# 3_IMU_ETH.net
KiCad netlist of a schematic drawn in Altium Designer
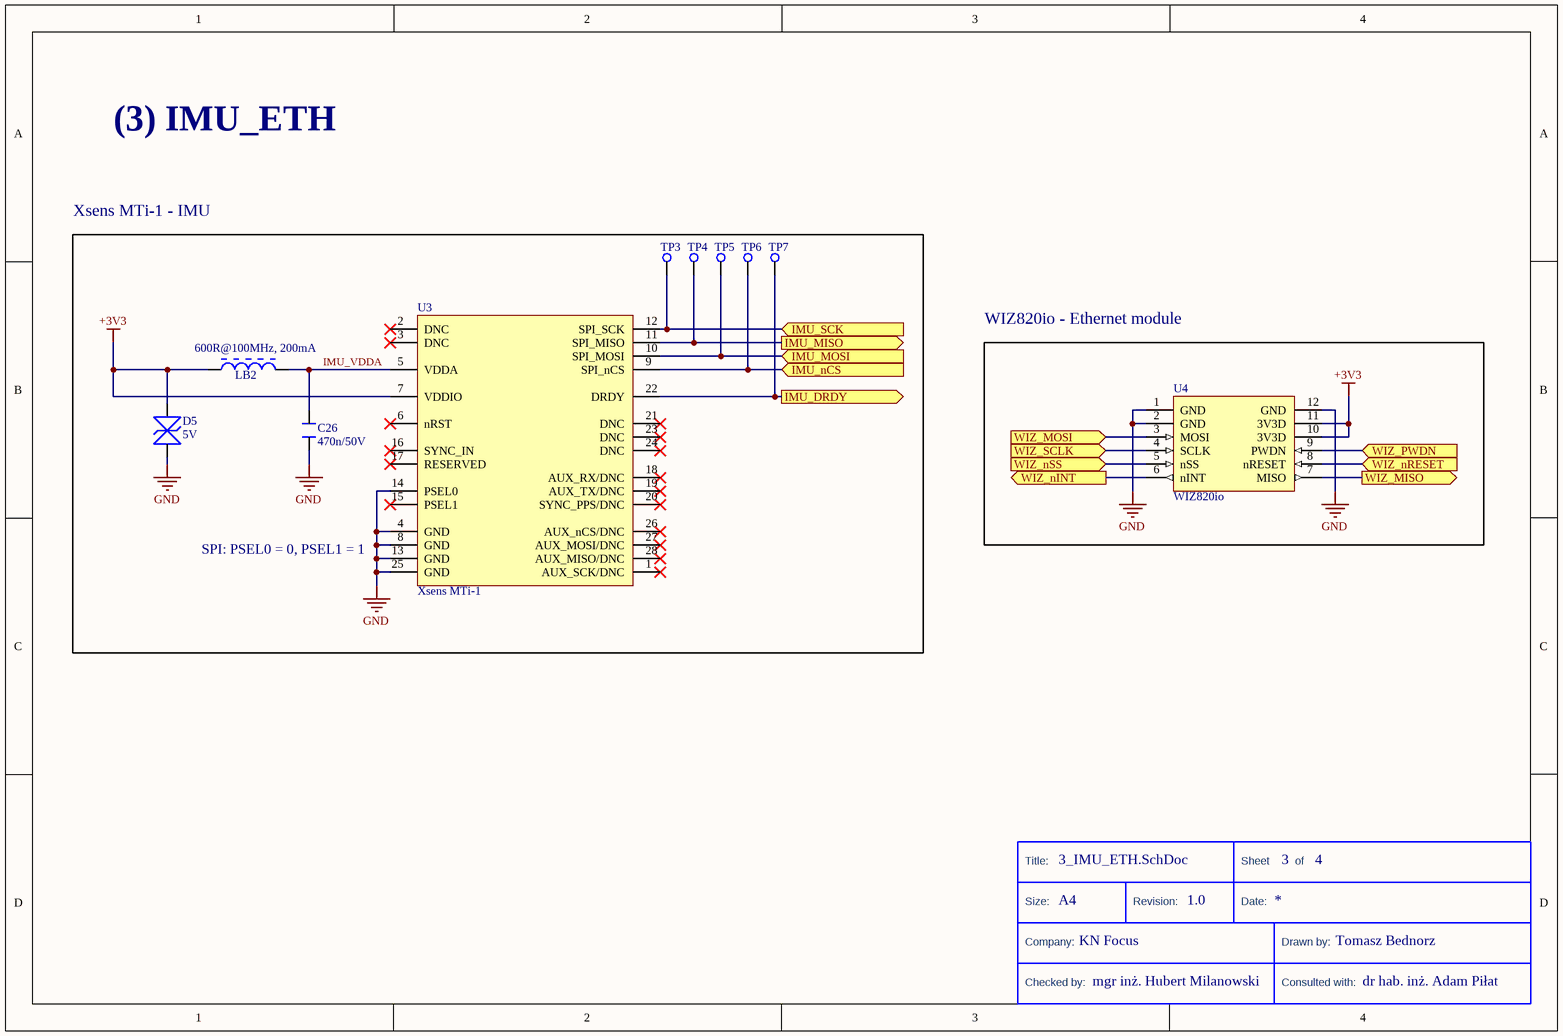
[diagram p0: 3_IMU_ETH.SchDoc]

(export (version "E")
  (design (tool "Eeschema 10.0.6"))
  (components
    (comp (ref "C26")
      (value "470n/50V")
      (footprint "CAP_1206")
      (description "Generic 1206/3216 capacitor")
      (libsource (lib "SymbolLib") (part "CAP_1206"))
    )
    (comp (ref "D5")
      (value "5V")
      (footprint "TVS_Littlefuse")
      (description "TVS Diode TVS_SMAJ5.0CA  5V Bidirectional")
      (libsource (lib "SymbolLib") (part "TVS_5V"))
    )
    (comp (ref "LB2")
      (value "600R@100MHz, 200mA")
      (footprint "MURA-BLM31A_L")
      (fields (field (name "TOLERANCE") "25%") (field (name "MANUFACTURER") "Murata"))
      (libsource (lib "Altium Content Vault") (part "IND-FB-2"))
    )
    (comp (ref "TP3")
      (value "TestPoint Pad 1.0mmx1.0mm")
      (footprint "TestPoint Pad 1.0mmx1.0mm")
      (libsource (lib "SymbolLib") (part "TestPoint Pad 1.0mmx1.0mm"))
    )
    (comp (ref "TP4")
      (value "TestPoint Pad 1.0mmx1.0mm")
      (footprint "TestPoint Pad 1.0mmx1.0mm")
      (libsource (lib "SymbolLib") (part "TestPoint Pad 1.0mmx1.0mm"))
    )
    (comp (ref "TP5")
      (value "TestPoint Pad 1.0mmx1.0mm")
      (footprint "TestPoint Pad 1.0mmx1.0mm")
      (libsource (lib "SymbolLib") (part "TestPoint Pad 1.0mmx1.0mm"))
    )
    (comp (ref "TP6")
      (value "TestPoint Pad 1.0mmx1.0mm")
      (footprint "TestPoint Pad 1.0mmx1.0mm")
      (libsource (lib "SymbolLib") (part "TestPoint Pad 1.0mmx1.0mm"))
    )
    (comp (ref "TP7")
      (value "TestPoint Pad 1.0mmx1.0mm")
      (footprint "TestPoint Pad 1.0mmx1.0mm")
      (libsource (lib "SymbolLib") (part "TestPoint Pad 1.0mmx1.0mm"))
    )
    (comp (ref "U3")
      (value "Xsens MTi-1")
      (footprint "PLCC-28SMD 1.27MM NINIGI")
      (description "PLCC-28SMD socket for Xsens MTi-1 (SPI)")
      (libsource (lib "SymbolLib") (part "Xsens MTi-1"))
    )
    (comp (ref "U4")
      (value "WIZ820io")
      (footprint "2x6 Header - 20.32 gap")
      (description "2x6 Famale Header for WIZ820io ETH controller (W5200)")
      (libsource (lib "SymbolLib") (part "WIZ820io"))
    )
  )
  (nets
    (net (code "1") (name "+3V3") (class "Default")
      (node (ref "D5") (pin "1") (pinfunction "1_1") (pintype "passive"))
      (node (ref "LB2") (pin "1") (pinfunction "1_1") (pintype "passive"))
      (node (ref "U3") (pin "7") (pinfunction "VDDIO_7") (pintype "passive"))
      (node (ref "U4") (pin "10") (pinfunction "3V3D_10") (pintype "passive"))
      (node (ref "U4") (pin "11") (pinfunction "3V3D_11") (pintype "passive"))
    )
    (net (code "2") (name "/IMU_DRDY") (class "Default")
      (node (ref "TP7") (pin "1") (pinfunction "1_1") (pintype "passive"))
      (node (ref "U3") (pin "22") (pinfunction "DRDY_22") (pintype "passive"))
    )
    (net (code "3") (name "/IMU_MISO") (class "Default")
      (node (ref "TP4") (pin "1") (pinfunction "1_1") (pintype "passive"))
      (node (ref "U3") (pin "11") (pinfunction "SPI_MISO_11") (pintype "passive"))
    )
    (net (code "4") (name "/IMU_MOSI") (class "Default")
      (node (ref "TP5") (pin "1") (pinfunction "1_1") (pintype "passive"))
      (node (ref "U3") (pin "10") (pinfunction "SPI_MOSI_10") (pintype "passive"))
    )
    (net (code "5") (name "/IMU_SCK") (class "Default")
      (node (ref "TP3") (pin "1") (pinfunction "1_1") (pintype "passive"))
      (node (ref "U3") (pin "12") (pinfunction "SPI_SCK_12") (pintype "passive"))
    )
    (net (code "6") (name "/IMU_VDDA") (class "Default")
      (node (ref "C26") (pin "2") (pinfunction "2_2") (pintype "passive"))
      (node (ref "LB2") (pin "2") (pinfunction "2_2") (pintype "passive"))
      (node (ref "U3") (pin "5") (pinfunction "VDDA_5") (pintype "passive"))
    )
    (net (code "7") (name "/IMU_nCS") (class "Default")
      (node (ref "TP6") (pin "1") (pinfunction "1_1") (pintype "passive"))
      (node (ref "U3") (pin "9") (pinfunction "SPI_nCS_9") (pintype "passive"))
    )
    (net (code "8") (name "/WIZ_MISO") (class "Default")
      (node (ref "U4") (pin "7") (pinfunction "MISO_7") (pintype "output"))
    )
    (net (code "9") (name "/WIZ_MOSI") (class "Default")
      (node (ref "U4") (pin "3") (pinfunction "MOSI_3") (pintype "input"))
    )
    (net (code "10") (name "/WIZ_PWDN") (class "Default")
      (node (ref "U4") (pin "9") (pinfunction "PWDN_9") (pintype "input"))
    )
    (net (code "11") (name "/WIZ_SCLK") (class "Default")
      (node (ref "U4") (pin "4") (pinfunction "SCLK_4") (pintype "input"))
    )
    (net (code "12") (name "/WIZ_nINT") (class "Default")
      (node (ref "U4") (pin "6") (pinfunction "nINT_6") (pintype "output"))
    )
    (net (code "13") (name "/WIZ_nRESET") (class "Default")
      (node (ref "U4") (pin "8") (pinfunction "nRESET_8") (pintype "input"))
    )
    (net (code "14") (name "/WIZ_nSS") (class "Default")
      (node (ref "U4") (pin "5") (pinfunction "nSS_5") (pintype "input"))
    )
    (net (code "15") (name "GND") (class "Default")
      (node (ref "C26") (pin "1") (pinfunction "1_1") (pintype "passive"))
      (node (ref "D5") (pin "2") (pinfunction "2_2") (pintype "passive"))
      (node (ref "U3") (pin "13") (pinfunction "GND_13") (pintype "passive"))
      (node (ref "U3") (pin "14") (pinfunction "PSEL0_14") (pintype "passive"))
      (node (ref "U3") (pin "25") (pinfunction "GND_25") (pintype "passive"))
      (node (ref "U3") (pin "4") (pinfunction "GND_4") (pintype "passive"))
      (node (ref "U3") (pin "8") (pinfunction "GND_8") (pintype "passive"))
      (node (ref "U4") (pin "1") (pinfunction "GND_1") (pintype "passive"))
      (node (ref "U4") (pin "12") (pinfunction "GND_12") (pintype "passive"))
      (node (ref "U4") (pin "2") (pinfunction "GND_2") (pintype "passive"))
    )
    (net (code "16") (name "unconnected-(U3-AUX_MISO{slash}DNC-Pad28)") (class "Default")
      (node (ref "U3") (pin "28") (pinfunction "AUX_MISO/DNC_28") (pintype "passive+no_connect"))
    )
    (net (code "17") (name "unconnected-(U3-AUX_MOSI{slash}DNC-Pad27)") (class "Default")
      (node (ref "U3") (pin "27") (pinfunction "AUX_MOSI/DNC_27") (pintype "passive+no_connect"))
    )
    (net (code "18") (name "unconnected-(U3-AUX_RX{slash}DNC-Pad18)") (class "Default")
      (node (ref "U3") (pin "18") (pinfunction "AUX_RX/DNC_18") (pintype "passive+no_connect"))
    )
    (net (code "19") (name "unconnected-(U3-AUX_SCK{slash}DNC-Pad1)") (class "Default")
      (node (ref "U3") (pin "1") (pinfunction "AUX_SCK/DNC_1") (pintype "passive+no_connect"))
    )
    (net (code "20") (name "unconnected-(U3-AUX_TX{slash}DNC-Pad19)") (class "Default")
      (node (ref "U3") (pin "19") (pinfunction "AUX_TX/DNC_19") (pintype "passive+no_connect"))
    )
    (net (code "21") (name "unconnected-(U3-AUX_nCS{slash}DNC-Pad26)") (class "Default")
      (node (ref "U3") (pin "26") (pinfunction "AUX_nCS/DNC_26") (pintype "passive+no_connect"))
    )
    (net (code "22") (name "unconnected-(U3-DNC-Pad2)") (class "Default")
      (node (ref "U3") (pin "2") (pinfunction "DNC_2") (pintype "passive+no_connect"))
    )
    (net (code "23") (name "unconnected-(U3-DNC-Pad3)") (class "Default")
      (node (ref "U3") (pin "3") (pinfunction "DNC_3") (pintype "passive+no_connect"))
    )
    (net (code "24") (name "unconnected-(U3-DNC-Pad21)") (class "Default")
      (node (ref "U3") (pin "21") (pinfunction "DNC_21") (pintype "passive+no_connect"))
    )
    (net (code "25") (name "unconnected-(U3-DNC-Pad23)") (class "Default")
      (node (ref "U3") (pin "23") (pinfunction "DNC_23") (pintype "passive+no_connect"))
    )
    (net (code "26") (name "unconnected-(U3-DNC-Pad24)") (class "Default")
      (node (ref "U3") (pin "24") (pinfunction "DNC_24") (pintype "passive+no_connect"))
    )
    (net (code "27") (name "unconnected-(U3-PSEL1-Pad15)") (class "Default")
      (node (ref "U3") (pin "15") (pinfunction "PSEL1_15") (pintype "passive+no_connect"))
    )
    (net (code "28") (name "unconnected-(U3-RESERVED-Pad17)") (class "Default")
      (node (ref "U3") (pin "17") (pinfunction "RESERVED_17") (pintype "passive+no_connect"))
    )
    (net (code "29") (name "unconnected-(U3-SYNC_IN-Pad16)") (class "Default")
      (node (ref "U3") (pin "16") (pinfunction "SYNC_IN_16") (pintype "passive+no_connect"))
    )
    (net (code "30") (name "unconnected-(U3-SYNC_PPS{slash}DNC-Pad20)") (class "Default")
      (node (ref "U3") (pin "20") (pinfunction "SYNC_PPS/DNC_20") (pintype "passive+no_connect"))
    )
    (net (code "31") (name "unconnected-(U3-nRST-Pad6)") (class "Default")
      (node (ref "U3") (pin "6") (pinfunction "nRST_6") (pintype "passive+no_connect"))
    )
  )
)
